# PowerMeterShield.net
KiCad netlist of a schematic drawn in EAGLE
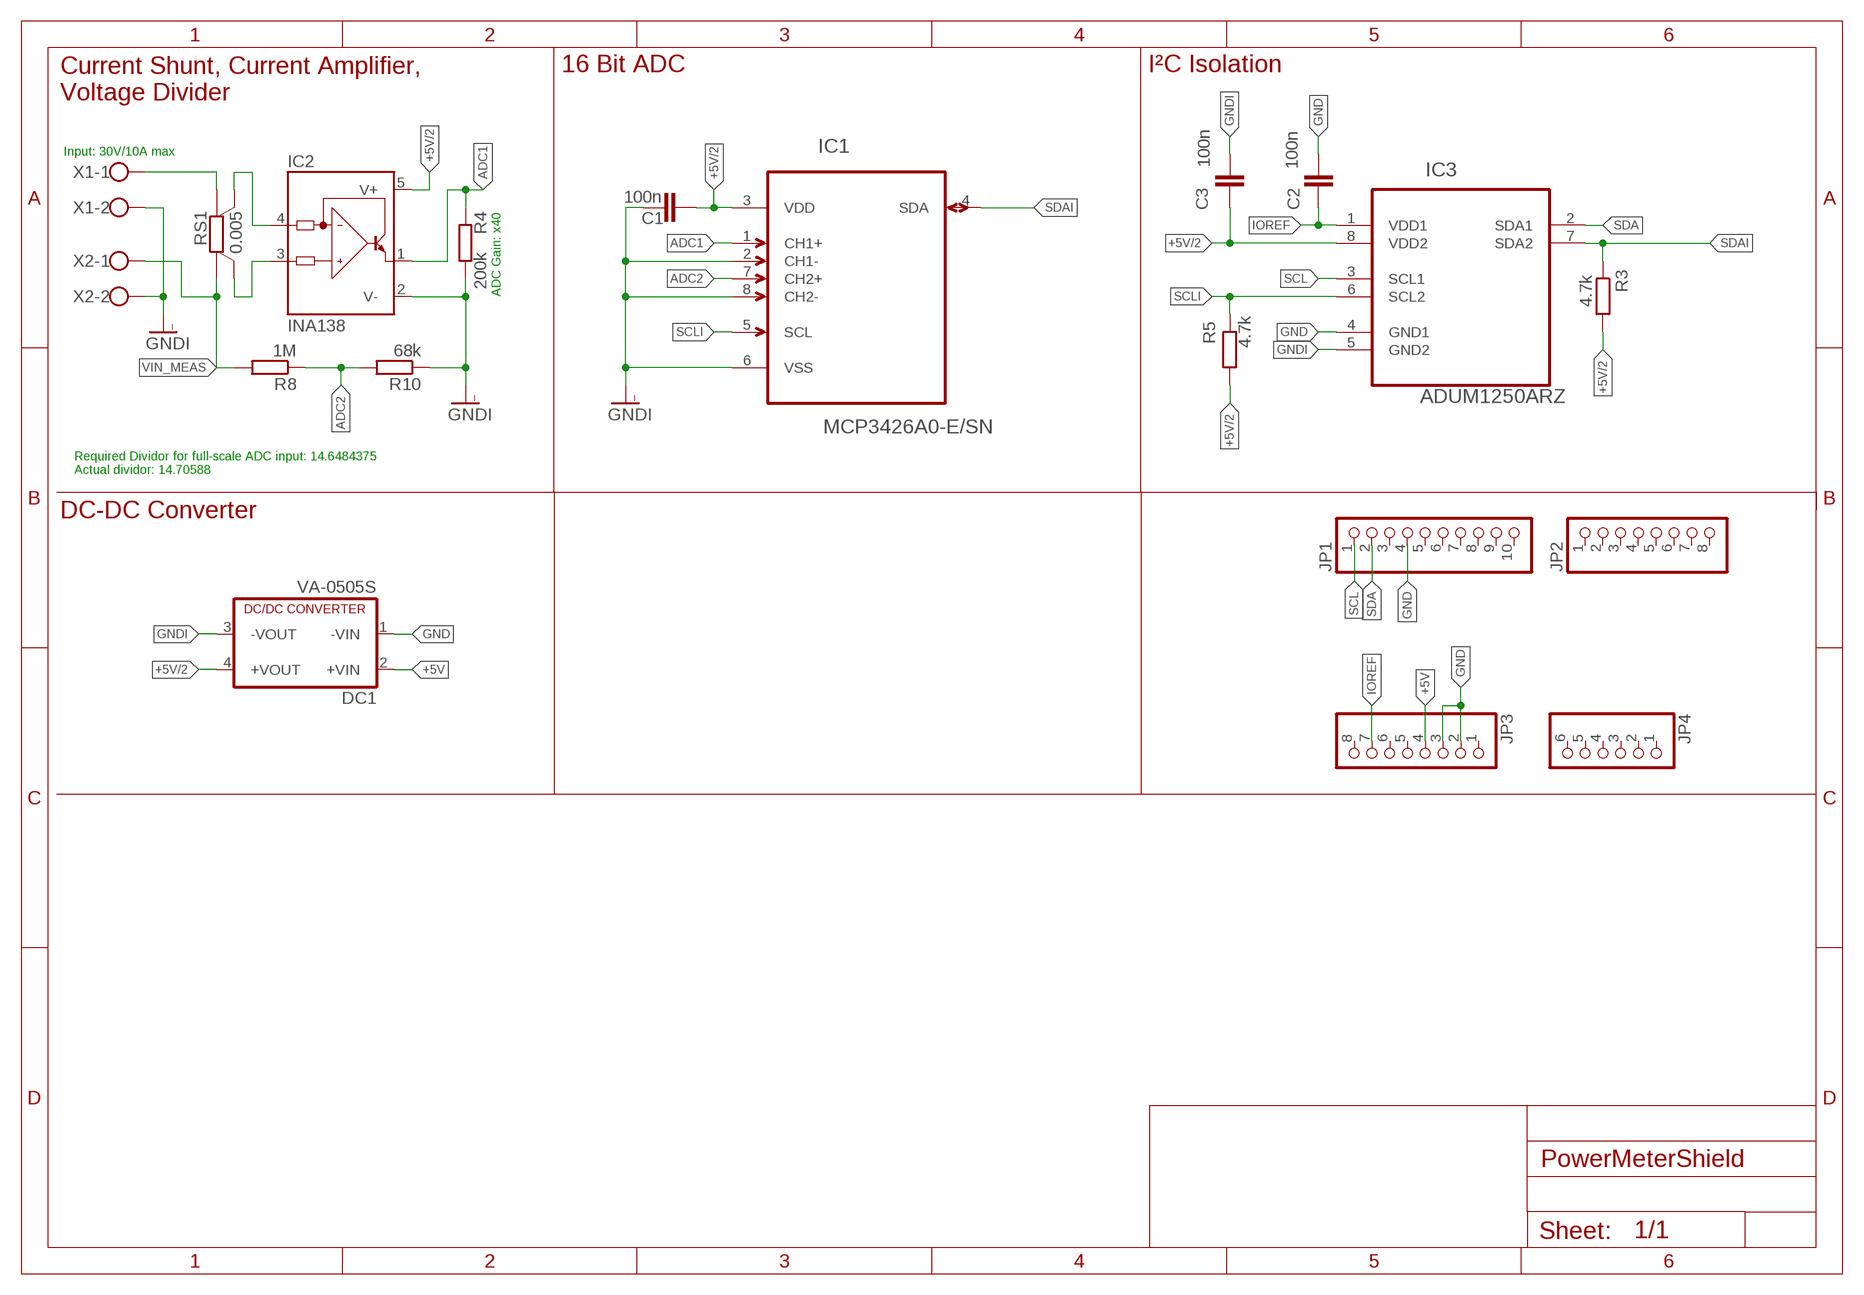
[diagram p0: schematic, sheet 1]

(export (version "E")
  (design (tool "Eeschema 10.0.6"))
  (components
    (comp (ref "C1")
      (value "100n")
      (footprint "eagle-import:C0805")
      (libsource (lib "eagle-import") (part "C-EUC0805"))
    )
    (comp (ref "C2")
      (value "100n")
      (footprint "eagle-import:C0805")
      (libsource (lib "eagle-import") (part "C-EUC0805"))
    )
    (comp (ref "C3")
      (value "100n")
      (footprint "eagle-import:C0805")
      (libsource (lib "eagle-import") (part "C-EUC0805"))
    )
    (comp (ref "DC1")
      (value "VA-0505S")
      (footprint "eagle-import:4SIL")
      (fields (field (name "OC_FARNELL") "2079696"))
      (libsource (lib "eagle-import") (part "VA-?S0505"))
    )
    (comp (ref "IC1")
      (value "MCP3426A0-E/SN")
      (footprint "eagle-import:SOIC127P600X175-8N")
      (libsource (lib "eagle-import") (part "MCP3426A0-E/SN"))
    )
    (comp (ref "IC2")
      (value "INA138")
      (footprint "eagle-import:SOT23-5")
      (fields
        (field (name "MF") "TEXAS INSTRUMENTS")
        (field (name "MPN") "INA138NA/250")
        (field (name "OC_FARNELL") "1206900RL")
      )
      (libsource (lib "eagle-import") (part "INA138"))
    )
    (comp (ref "IC3")
      (value "ADUM1250ARZ")
      (footprint "eagle-import:SOIC127P600X175-8N")
      (libsource (lib "eagle-import") (part "ADUM1250ARZ"))
    )
    (comp (ref "JP1")
      (value "PINHD-1X10")
      (footprint "eagle-import:1X10")
      (libsource (lib "eagle-import") (part "PINHD-1X10"))
    )
    (comp (ref "JP2")
      (value "PINHD-1X8")
      (footprint "eagle-import:1X08")
      (libsource (lib "eagle-import") (part "PINHD-1X8"))
    )
    (comp (ref "JP3")
      (value "PINHD-1X8")
      (footprint "eagle-import:1X08")
      (libsource (lib "eagle-import") (part "PINHD-1X8"))
    )
    (comp (ref "JP4")
      (value "PINHD-1X6")
      (footprint "eagle-import:1X06")
      (libsource (lib "eagle-import") (part "PINHD-1X6"))
    )
    (comp (ref "R3")
      (value "4.7k")
      (footprint "eagle-import:R0805")
      (libsource (lib "eagle-import") (part "R-EU_R0805"))
    )
    (comp (ref "R4")
      (value "200k")
      (footprint "eagle-import:R0805")
      (libsource (lib "eagle-import") (part "R-EU_R0805"))
    )
    (comp (ref "R5")
      (value "4.7k")
      (footprint "eagle-import:R0805")
      (libsource (lib "eagle-import") (part "R-EU_R0805"))
    )
    (comp (ref "R8")
      (value "1M")
      (footprint "eagle-import:R0805")
      (libsource (lib "eagle-import") (part "R-EU_R0805"))
    )
    (comp (ref "R10")
      (value "68k")
      (footprint "eagle-import:R0805")
      (libsource (lib "eagle-import") (part "R-EU_R0805"))
    )
    (comp (ref "RS1")
      (value "0.005")
      (footprint "eagle-import:CSM3637M")
      (libsource (lib "eagle-import") (part "SHUNT-4CSM3675M"))
    )
    (comp (ref "X1")
      (value "W237-102")
      (footprint "eagle-import:W237-102")
      (fields
        (field (name "MPN") "237-102")
        (field (name "OC_FARNELL") "1717001")
        (field (name "PRICE_10") "0.294")
      )
      (libsource (lib "eagle-import") (part "W237-102"))
    )
    (comp (ref "X2")
      (value "W237-102")
      (footprint "eagle-import:W237-102")
      (fields
        (field (name "MPN") "237-102")
        (field (name "OC_FARNELL") "1717001")
        (field (name "PRICE_10") "0.294")
      )
      (libsource (lib "eagle-import") (part "W237-102"))
    )
  )
  (nets
    (net (code "1") (name "+5V") (class "Default")
      (node (ref "DC1") (pin "2") (pinfunction "+VIN_2") (pintype "passive"))
      (node (ref "JP3") (pin "4") (pinfunction "4_4") (pintype "passive"))
    )
    (net (code "2") (name "+5V{slash}2") (class "Default")
      (node (ref "C1") (pin "1") (pinfunction "1_1") (pintype "passive"))
      (node (ref "C3") (pin "1") (pinfunction "1_1") (pintype "passive"))
      (node (ref "DC1") (pin "4") (pinfunction "+VOUT_4") (pintype "passive"))
      (node (ref "IC1") (pin "3") (pinfunction "VDD_3") (pintype "power_in"))
      (node (ref "IC2") (pin "5") (pinfunction "V+_5") (pintype "power_in"))
      (node (ref "IC3") (pin "8") (pinfunction "VDD2_8") (pintype "power_in"))
      (node (ref "R3") (pin "2") (pinfunction "2_2") (pintype "passive"))
      (node (ref "R5") (pin "2") (pinfunction "2_2") (pintype "passive"))
    )
    (net (code "3") (name "ADC1") (class "Default")
      (node (ref "IC1") (pin "1") (pinfunction "CH1+_1") (pintype "input"))
      (node (ref "IC2") (pin "1") (pinfunction "OUT_1") (pintype "output"))
      (node (ref "R4") (pin "2") (pinfunction "2_2") (pintype "passive"))
    )
    (net (code "4") (name "ADC2") (class "Default")
      (node (ref "IC1") (pin "7") (pinfunction "CH2+_7") (pintype "input"))
      (node (ref "R10") (pin "2") (pinfunction "2_2") (pintype "passive"))
      (node (ref "R8") (pin "1") (pinfunction "1_1") (pintype "passive"))
    )
    (net (code "5") (name "GND") (class "Default")
      (node (ref "C2") (pin "2") (pinfunction "2_2") (pintype "passive"))
      (node (ref "DC1") (pin "1") (pinfunction "-VIN_1") (pintype "passive"))
      (node (ref "IC3") (pin "4") (pinfunction "GND1_4") (pintype "passive"))
      (node (ref "JP1") (pin "4") (pinfunction "4_4") (pintype "passive"))
      (node (ref "JP3") (pin "2") (pinfunction "2_2") (pintype "passive"))
      (node (ref "JP3") (pin "3") (pinfunction "3_3") (pintype "passive"))
    )
    (net (code "6") (name "GNDI") (class "Default")
      (node (ref "C1") (pin "2") (pinfunction "2_2") (pintype "passive"))
      (node (ref "C3") (pin "2") (pinfunction "2_2") (pintype "passive"))
      (node (ref "DC1") (pin "3") (pinfunction "-VOUT_3") (pintype "passive"))
      (node (ref "IC1") (pin "2") (pinfunction "CH1-_2") (pintype "input"))
      (node (ref "IC1") (pin "6") (pinfunction "VSS_6") (pintype "power_in"))
      (node (ref "IC1") (pin "8") (pinfunction "CH2-_8") (pintype "input"))
      (node (ref "IC2") (pin "2") (pinfunction "V-_2") (pintype "power_in"))
      (node (ref "IC3") (pin "5") (pinfunction "GND2_5") (pintype "passive"))
      (node (ref "R10") (pin "1") (pinfunction "1_1") (pintype "passive"))
      (node (ref "R4") (pin "1") (pinfunction "1_1") (pintype "passive"))
      (node (ref "X1") (pin "2") (pinfunction "KL_2") (pintype "passive"))
      (node (ref "X2") (pin "2") (pinfunction "KL_2") (pintype "passive"))
    )
    (net (code "7") (name "IOREF") (class "Default")
      (node (ref "C2") (pin "1") (pinfunction "1_1") (pintype "passive"))
      (node (ref "IC3") (pin "1") (pinfunction "VDD1_1") (pintype "power_in"))
      (node (ref "JP3") (pin "7") (pinfunction "7_7") (pintype "passive"))
    )
    (net (code "8") (name "Net-(IC2-IN+)") (class "Default")
      (node (ref "IC2") (pin "3") (pinfunction "IN+_3") (pintype "input"))
      (node (ref "RS1") (pin "S1") (pinfunction "S1_S1") (pintype "passive"))
    )
    (net (code "9") (name "Net-(IC2-IN-)") (class "Default")
      (node (ref "IC2") (pin "4") (pinfunction "IN-_4") (pintype "input"))
      (node (ref "RS1") (pin "S2") (pinfunction "S2_S2") (pintype "passive"))
    )
    (net (code "10") (name "Net-(X1A-KL)") (class "Default")
      (node (ref "RS1") (pin "I2") (pinfunction "I2_I2") (pintype "passive"))
      (node (ref "X1") (pin "1") (pinfunction "KL_1") (pintype "passive"))
    )
    (net (code "11") (name "SCL") (class "Default")
      (node (ref "IC3") (pin "3") (pinfunction "SCL1_3") (pintype "input"))
      (node (ref "JP1") (pin "1") (pinfunction "1_1") (pintype "passive"))
    )
    (net (code "12") (name "SCLI") (class "Default")
      (node (ref "IC1") (pin "5") (pinfunction "SCL_5") (pintype "input"))
      (node (ref "IC3") (pin "6") (pinfunction "SCL2_6") (pintype "input"))
      (node (ref "R5") (pin "1") (pinfunction "1_1") (pintype "passive"))
    )
    (net (code "13") (name "SDA") (class "Default")
      (node (ref "IC3") (pin "2") (pinfunction "SDA1_2") (pintype "bidirectional"))
      (node (ref "JP1") (pin "2") (pinfunction "2_2") (pintype "passive"))
    )
    (net (code "14") (name "SDAI") (class "Default")
      (node (ref "IC1") (pin "4") (pinfunction "SDA_4") (pintype "bidirectional"))
      (node (ref "IC3") (pin "7") (pinfunction "SDA2_7") (pintype "bidirectional"))
      (node (ref "R3") (pin "1") (pinfunction "1_1") (pintype "passive"))
    )
    (net (code "15") (name "VIN_MEAS") (class "Default")
      (node (ref "R8") (pin "2") (pinfunction "2_2") (pintype "passive"))
      (node (ref "RS1") (pin "I1") (pinfunction "I1_I1") (pintype "passive"))
      (node (ref "X2") (pin "1") (pinfunction "KL_1") (pintype "passive"))
    )
    (net (code "16") (name "unconnected-(JP1-Pad3)") (class "Default")
      (node (ref "JP1") (pin "3") (pinfunction "3_3") (pintype "passive"))
    )
    (net (code "17") (name "unconnected-(JP1-Pad5)") (class "Default")
      (node (ref "JP1") (pin "5") (pinfunction "5_5") (pintype "passive"))
    )
    (net (code "18") (name "unconnected-(JP1-Pad6)") (class "Default")
      (node (ref "JP1") (pin "6") (pinfunction "6_6") (pintype "passive"))
    )
    (net (code "19") (name "unconnected-(JP1-Pad7)") (class "Default")
      (node (ref "JP1") (pin "7") (pinfunction "7_7") (pintype "passive"))
    )
    (net (code "20") (name "unconnected-(JP1-Pad8)") (class "Default")
      (node (ref "JP1") (pin "8") (pinfunction "8_8") (pintype "passive"))
    )
    (net (code "21") (name "unconnected-(JP1-Pad9)") (class "Default")
      (node (ref "JP1") (pin "9") (pinfunction "9_9") (pintype "passive"))
    )
    (net (code "22") (name "unconnected-(JP1-Pad10)") (class "Default")
      (node (ref "JP1") (pin "10") (pinfunction "10_10") (pintype "passive"))
    )
    (net (code "23") (name "unconnected-(JP2-Pad1)") (class "Default")
      (node (ref "JP2") (pin "1") (pinfunction "1_1") (pintype "passive"))
    )
    (net (code "24") (name "unconnected-(JP2-Pad2)") (class "Default")
      (node (ref "JP2") (pin "2") (pinfunction "2_2") (pintype "passive"))
    )
    (net (code "25") (name "unconnected-(JP2-Pad3)") (class "Default")
      (node (ref "JP2") (pin "3") (pinfunction "3_3") (pintype "passive"))
    )
    (net (code "26") (name "unconnected-(JP2-Pad4)") (class "Default")
      (node (ref "JP2") (pin "4") (pinfunction "4_4") (pintype "passive"))
    )
    (net (code "27") (name "unconnected-(JP2-Pad5)") (class "Default")
      (node (ref "JP2") (pin "5") (pinfunction "5_5") (pintype "passive"))
    )
    (net (code "28") (name "unconnected-(JP2-Pad6)") (class "Default")
      (node (ref "JP2") (pin "6") (pinfunction "6_6") (pintype "passive"))
    )
    (net (code "29") (name "unconnected-(JP2-Pad7)") (class "Default")
      (node (ref "JP2") (pin "7") (pinfunction "7_7") (pintype "passive"))
    )
    (net (code "30") (name "unconnected-(JP2-Pad8)") (class "Default")
      (node (ref "JP2") (pin "8") (pinfunction "8_8") (pintype "passive"))
    )
    (net (code "31") (name "unconnected-(JP3-Pad1)") (class "Default")
      (node (ref "JP3") (pin "1") (pinfunction "1_1") (pintype "passive"))
    )
    (net (code "32") (name "unconnected-(JP3-Pad5)") (class "Default")
      (node (ref "JP3") (pin "5") (pinfunction "5_5") (pintype "passive"))
    )
    (net (code "33") (name "unconnected-(JP3-Pad6)") (class "Default")
      (node (ref "JP3") (pin "6") (pinfunction "6_6") (pintype "passive"))
    )
    (net (code "34") (name "unconnected-(JP3-Pad8)") (class "Default")
      (node (ref "JP3") (pin "8") (pinfunction "8_8") (pintype "passive"))
    )
    (net (code "35") (name "unconnected-(JP4-Pad1)") (class "Default")
      (node (ref "JP4") (pin "1") (pinfunction "1_1") (pintype "passive"))
    )
    (net (code "36") (name "unconnected-(JP4-Pad2)") (class "Default")
      (node (ref "JP4") (pin "2") (pinfunction "2_2") (pintype "passive"))
    )
    (net (code "37") (name "unconnected-(JP4-Pad3)") (class "Default")
      (node (ref "JP4") (pin "3") (pinfunction "3_3") (pintype "passive"))
    )
    (net (code "38") (name "unconnected-(JP4-Pad4)") (class "Default")
      (node (ref "JP4") (pin "4") (pinfunction "4_4") (pintype "passive"))
    )
    (net (code "39") (name "unconnected-(JP4-Pad5)") (class "Default")
      (node (ref "JP4") (pin "5") (pinfunction "5_5") (pintype "passive"))
    )
    (net (code "40") (name "unconnected-(JP4-Pad6)") (class "Default")
      (node (ref "JP4") (pin "6") (pinfunction "6_6") (pintype "passive"))
    )
  )
)
